# Reader1.net
KiCad netlist of a schematic drawn in EAGLE
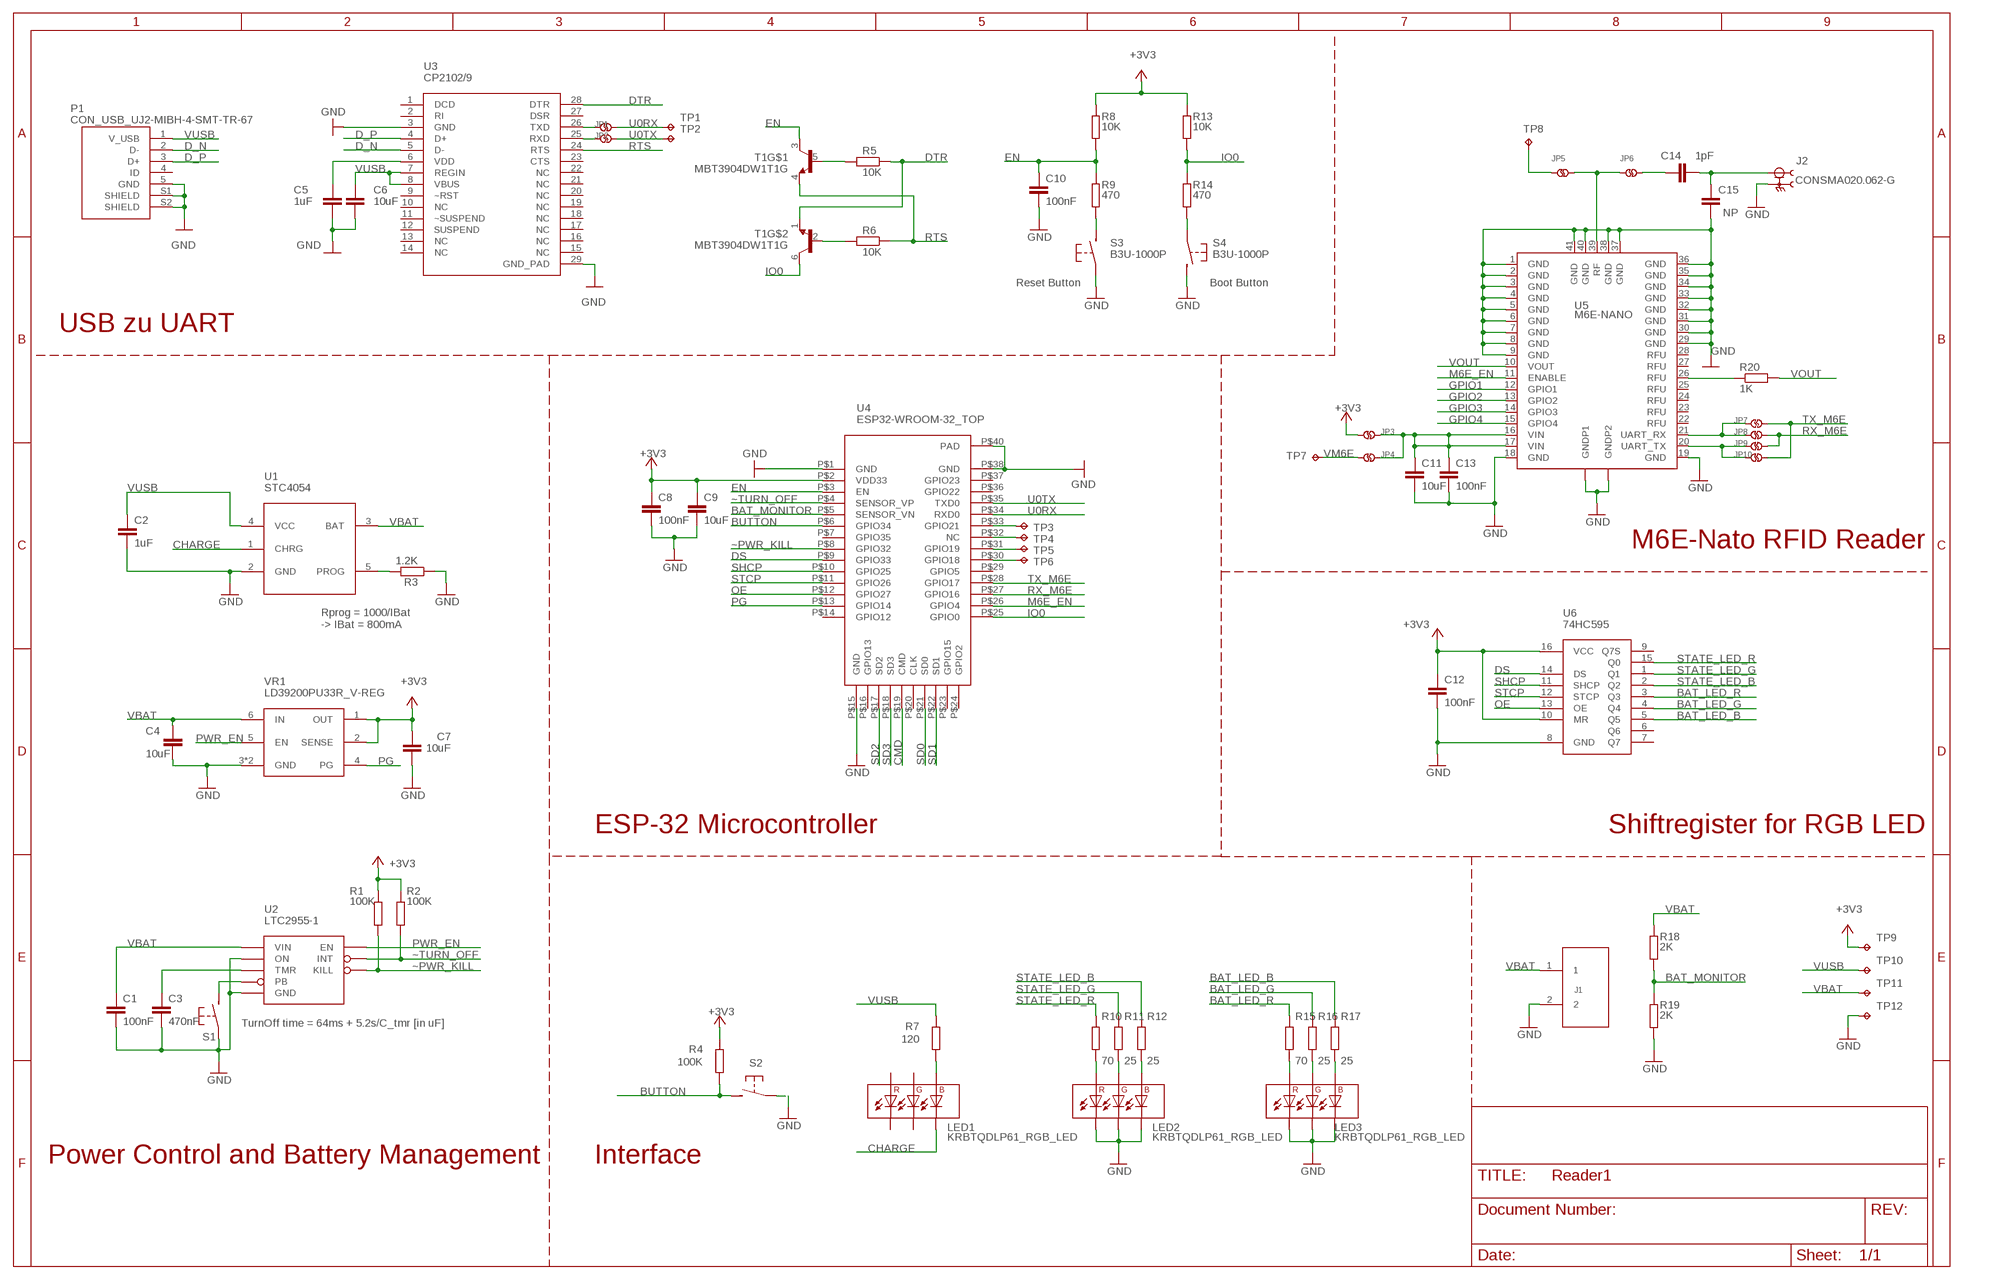
[diagram p0: schematic, sheet 1]

(export (version "E")
  (design (tool "Eeschema 10.0.6"))
  (components
    (comp (ref "C1")
      (value "100nF")
      (footprint "eagle-import:0603")
      (libsource (lib "eagle-import") (part "CAP_0603"))
    )
    (comp (ref "C2")
      (value "1uF")
      (footprint "eagle-import:0603")
      (libsource (lib "eagle-import") (part "CAP_0603"))
    )
    (comp (ref "C3")
      (value "470nF")
      (footprint "eagle-import:0603")
      (libsource (lib "eagle-import") (part "CAP_0603"))
    )
    (comp (ref "C4")
      (value "10uF")
      (footprint "eagle-import:0603")
      (libsource (lib "eagle-import") (part "CAP_0603"))
    )
    (comp (ref "C5")
      (value "1uF")
      (footprint "eagle-import:0603")
      (libsource (lib "eagle-import") (part "CAP_0603"))
    )
    (comp (ref "C6")
      (value "10uF")
      (footprint "eagle-import:0603")
      (libsource (lib "eagle-import") (part "CAP_0603"))
    )
    (comp (ref "C7")
      (value "10uF")
      (footprint "eagle-import:0603")
      (libsource (lib "eagle-import") (part "CAP_0603"))
    )
    (comp (ref "C8")
      (value "100nF")
      (footprint "eagle-import:0603")
      (libsource (lib "eagle-import") (part "CAP_0603"))
    )
    (comp (ref "C9")
      (value "10uF")
      (footprint "eagle-import:0603")
      (libsource (lib "eagle-import") (part "CAP_0603"))
    )
    (comp (ref "C10")
      (value "100nF")
      (footprint "eagle-import:0603")
      (libsource (lib "eagle-import") (part "CAP_0603"))
    )
    (comp (ref "C11")
      (value "10uF")
      (footprint "eagle-import:0603")
      (libsource (lib "eagle-import") (part "CAP_0603"))
    )
    (comp (ref "C12")
      (value "100nF")
      (footprint "eagle-import:0603")
      (libsource (lib "eagle-import") (part "CAP_0603"))
    )
    (comp (ref "C13")
      (value "100nF")
      (footprint "eagle-import:0603")
      (libsource (lib "eagle-import") (part "CAP_0603"))
    )
    (comp (ref "C14")
      (value "1pF")
      (footprint "eagle-import:0603")
      (libsource (lib "eagle-import") (part "CAP_0603"))
    )
    (comp (ref "C15")
      (value "NP")
      (footprint "eagle-import:0603")
      (libsource (lib "eagle-import") (part "CAP_0603"))
    )
    (comp (ref "J1")
      (value "CON_2")
      (footprint "eagle-import:CON_2")
      (libsource (lib "eagle-import") (part "CON_2"))
    )
    (comp (ref "J2")
      (value "CONSMA020.062-G")
      (footprint "eagle-import:LINX_CONSMA020.062-G")
      (fields
        (field (name "DIGI-KEY_PART_NUMBER") "343-CONSMA020.062-G-ND")
        (field (name "MF") "Linx Technologies")
      )
      (libsource (lib "eagle-import") (part "CONSMA020.062-G"))
    )
    (comp (ref "JP1")
      (value "SOLDER_JUMPER")
      (footprint "eagle-import:SOLDER_JUMPER")
      (libsource (lib "eagle-import") (part "SOLDER_JUMPER"))
    )
    (comp (ref "JP2")
      (value "SOLDER_JUMPER")
      (footprint "eagle-import:SOLDER_JUMPER")
      (libsource (lib "eagle-import") (part "SOLDER_JUMPER"))
    )
    (comp (ref "JP3")
      (value "SOLDER_JUMPER")
      (footprint "eagle-import:SOLDER_JUMPER")
      (libsource (lib "eagle-import") (part "SOLDER_JUMPER"))
    )
    (comp (ref "JP4")
      (value "SOLDER_JUMPER")
      (footprint "eagle-import:SOLDER_JUMPER")
      (libsource (lib "eagle-import") (part "SOLDER_JUMPER"))
    )
    (comp (ref "JP5")
      (value "SOLDER_JUMPER")
      (footprint "eagle-import:SOLDER_JUMPER")
      (libsource (lib "eagle-import") (part "SOLDER_JUMPER"))
    )
    (comp (ref "JP6")
      (value "SOLDER_JUMPER")
      (footprint "eagle-import:SOLDER_JUMPER")
      (libsource (lib "eagle-import") (part "SOLDER_JUMPER"))
    )
    (comp (ref "JP7")
      (value "SOLDER_JUMPER")
      (footprint "eagle-import:SOLDER_JUMPER")
      (libsource (lib "eagle-import") (part "SOLDER_JUMPER"))
    )
    (comp (ref "JP8")
      (value "SOLDER_JUMPER")
      (footprint "eagle-import:SOLDER_JUMPER")
      (libsource (lib "eagle-import") (part "SOLDER_JUMPER"))
    )
    (comp (ref "JP9")
      (value "SOLDER_JUMPER")
      (footprint "eagle-import:SOLDER_JUMPER")
      (libsource (lib "eagle-import") (part "SOLDER_JUMPER"))
    )
    (comp (ref "JP10")
      (value "SOLDER_JUMPER")
      (footprint "eagle-import:SOLDER_JUMPER")
      (libsource (lib "eagle-import") (part "SOLDER_JUMPER"))
    )
    (comp (ref "LED1")
      (value "KRBTQDLP61_RGB_LED")
      (footprint "eagle-import:KRBTQDLP61_RGB_LED")
      (libsource (lib "eagle-import") (part "KRBTQDLP61_RGB_LED"))
    )
    (comp (ref "LED2")
      (value "KRBTQDLP61_RGB_LED")
      (footprint "eagle-import:KRBTQDLP61_RGB_LED")
      (libsource (lib "eagle-import") (part "KRBTQDLP61_RGB_LED"))
    )
    (comp (ref "LED3")
      (value "KRBTQDLP61_RGB_LED")
      (footprint "eagle-import:KRBTQDLP61_RGB_LED")
      (libsource (lib "eagle-import") (part "KRBTQDLP61_RGB_LED"))
    )
    (comp (ref "P1")
      (value "CON_USB_UJ2-MIBH-4-SMT-TR-67")
      (footprint "eagle-import:CON_USB_UJ2-MIBH-4-SMT-TR-67")
      (libsource (lib "eagle-import") (part "CON_USB_UJ2-MIBH-4-SMT-TR-67"))
    )
    (comp (ref "R1")
      (value "100K")
      (footprint "eagle-import:0603")
      (libsource (lib "eagle-import") (part "RES_0603"))
    )
    (comp (ref "R2")
      (value "100K")
      (footprint "eagle-import:0603")
      (libsource (lib "eagle-import") (part "RES_0603"))
    )
    (comp (ref "R3")
      (value "1.2K")
      (footprint "eagle-import:0603")
      (libsource (lib "eagle-import") (part "RES_0603"))
    )
    (comp (ref "R4")
      (value "100K")
      (footprint "eagle-import:0603")
      (libsource (lib "eagle-import") (part "RES_0603"))
    )
    (comp (ref "R5")
      (value "10K")
      (footprint "eagle-import:0603")
      (libsource (lib "eagle-import") (part "RES_0603"))
    )
    (comp (ref "R6")
      (value "10K")
      (footprint "eagle-import:0603")
      (libsource (lib "eagle-import") (part "RES_0603"))
    )
    (comp (ref "R7")
      (value "120")
      (footprint "eagle-import:0603")
      (libsource (lib "eagle-import") (part "RES_0603"))
    )
    (comp (ref "R8")
      (value "10K")
      (footprint "eagle-import:0603")
      (libsource (lib "eagle-import") (part "RES_0603"))
    )
    (comp (ref "R9")
      (value "470")
      (footprint "eagle-import:0603")
      (libsource (lib "eagle-import") (part "RES_0603"))
    )
    (comp (ref "R10")
      (value "70")
      (footprint "eagle-import:0603")
      (libsource (lib "eagle-import") (part "RES_0603"))
    )
    (comp (ref "R11")
      (value "25")
      (footprint "eagle-import:0603")
      (libsource (lib "eagle-import") (part "RES_0603"))
    )
    (comp (ref "R12")
      (value "25")
      (footprint "eagle-import:0603")
      (libsource (lib "eagle-import") (part "RES_0603"))
    )
    (comp (ref "R13")
      (value "10K")
      (footprint "eagle-import:0603")
      (libsource (lib "eagle-import") (part "RES_0603"))
    )
    (comp (ref "R14")
      (value "470")
      (footprint "eagle-import:0603")
      (libsource (lib "eagle-import") (part "RES_0603"))
    )
    (comp (ref "R15")
      (value "70")
      (footprint "eagle-import:0603")
      (libsource (lib "eagle-import") (part "RES_0603"))
    )
    (comp (ref "R16")
      (value "25")
      (footprint "eagle-import:0603")
      (libsource (lib "eagle-import") (part "RES_0603"))
    )
    (comp (ref "R17")
      (value "25")
      (footprint "eagle-import:0603")
      (libsource (lib "eagle-import") (part "RES_0603"))
    )
    (comp (ref "R18")
      (value "2K")
      (footprint "eagle-import:0603")
      (libsource (lib "eagle-import") (part "RES_0603"))
    )
    (comp (ref "R19")
      (value "2K")
      (footprint "eagle-import:0603")
      (libsource (lib "eagle-import") (part "RES_0603"))
    )
    (comp (ref "R20")
      (value "1K")
      (footprint "eagle-import:0603")
      (libsource (lib "eagle-import") (part "RES_0603"))
    )
    (comp (ref "S1")
      (value "EG5358CT-ND_PB")
      (footprint "eagle-import:EG5358CT-ND_PB")
      (libsource (lib "eagle-import") (part "EG5358CT-ND_PB"))
    )
    (comp (ref "S2")
      (value "EG5358CT-ND_PB")
      (footprint "eagle-import:EG5358CT-ND_PB")
      (libsource (lib "eagle-import") (part "EG5358CT-ND_PB"))
    )
    (comp (ref "S3")
      (value "B3U-1000P")
      (footprint "eagle-import:B3U-1000P")
      (libsource (lib "eagle-import") (part "BUTTON_B3U-1000P"))
    )
    (comp (ref "S4")
      (value "B3U-1000P")
      (footprint "eagle-import:B3U-1000P")
      (libsource (lib "eagle-import") (part "BUTTON_B3U-1000P"))
    )
    (comp (ref "T1")
      (value "MBT3904DW1T1G")
      (footprint "eagle-import:SOT23-6")
      (libsource (lib "eagle-import") (part "MBT3904DW1T1G"))
    )
    (comp (ref "TP1")
      (value "TP")
      (footprint "eagle-import:TEST_PAD")
      (libsource (lib "eagle-import") (part "TP"))
    )
    (comp (ref "TP2")
      (value "TP")
      (footprint "eagle-import:TEST_PAD")
      (libsource (lib "eagle-import") (part "TP"))
    )
    (comp (ref "TP3")
      (value "TP")
      (footprint "eagle-import:TEST_PAD")
      (libsource (lib "eagle-import") (part "TP"))
    )
    (comp (ref "TP4")
      (value "TP")
      (footprint "eagle-import:TEST_PAD")
      (libsource (lib "eagle-import") (part "TP"))
    )
    (comp (ref "TP5")
      (value "TP")
      (footprint "eagle-import:TEST_PAD")
      (libsource (lib "eagle-import") (part "TP"))
    )
    (comp (ref "TP6")
      (value "TP")
      (footprint "eagle-import:TEST_PAD")
      (libsource (lib "eagle-import") (part "TP"))
    )
    (comp (ref "TP7")
      (value "TP")
      (footprint "eagle-import:TEST_PAD")
      (libsource (lib "eagle-import") (part "TP"))
    )
    (comp (ref "TP8")
      (value "TP")
      (footprint "eagle-import:TEST_PAD")
      (libsource (lib "eagle-import") (part "TP"))
    )
    (comp (ref "TP9")
      (value "TP")
      (footprint "eagle-import:TEST_PAD")
      (libsource (lib "eagle-import") (part "TP"))
    )
    (comp (ref "TP10")
      (value "TP")
      (footprint "eagle-import:TEST_PAD")
      (libsource (lib "eagle-import") (part "TP"))
    )
    (comp (ref "TP11")
      (value "TP")
      (footprint "eagle-import:TEST_PAD")
      (libsource (lib "eagle-import") (part "TP"))
    )
    (comp (ref "TP12")
      (value "TP")
      (footprint "eagle-import:TEST_PAD")
      (libsource (lib "eagle-import") (part "TP"))
    )
    (comp (ref "U1")
      (value "STC4054")
      (footprint "eagle-import:TSOT23-5L")
      (libsource (lib "eagle-import") (part "STC4054_BAT_CHARGER"))
    )
    (comp (ref "U2")
      (value "LTC2955-1")
      (footprint "eagle-import:SOT23-8")
      (libsource (lib "eagle-import") (part "LTC2955-1_ON/OFF_CTLR"))
    )
    (comp (ref "U3")
      (value "CP2102/9")
      (footprint "eagle-import:QFN-28")
      (libsource (lib "eagle-import") (part "CP2102/9"))
    )
    (comp (ref "U4")
      (value "ESP32-WROOM-32_TOP")
      (footprint "eagle-import:ESP32-WROOM-32_TOP")
      (libsource (lib "eagle-import") (part "ESP32-WROOM-32_TOP"))
    )
    (comp (ref "U5")
      (value "M6E-NANO")
      (footprint "eagle-import:M6E-NANO")
      (libsource (lib "eagle-import") (part "M6E-NANO"))
    )
    (comp (ref "U6")
      (value "74HC595")
      (footprint "eagle-import:SOIC-16")
      (libsource (lib "eagle-import") (part "74HC595_SHIFTREGISTER"))
    )
    (comp (ref "VR1")
      (value "LD39200PU33R_V-REG")
      (footprint "eagle-import:DFN-6")
      (libsource (lib "eagle-import") (part "LD39200PU33R_V-REG"))
    )
  )
  (nets
    (net (code "1") (name "+3V3") (class "Default")
      (node (ref "C12") (pin "1") (pinfunction "1_1") (pintype "passive"))
      (node (ref "C7") (pin "2") (pinfunction "2_2") (pintype "passive"))
      (node (ref "C8") (pin "1") (pinfunction "1_1") (pintype "passive"))
      (node (ref "C9") (pin "1") (pinfunction "1_1") (pintype "passive"))
      (node (ref "JP3") (pin "P$1") (pinfunction "P$1_P$1") (pintype "bidirectional"))
      (node (ref "R1") (pin "1") (pinfunction "1_1") (pintype "passive"))
      (node (ref "R13") (pin "2") (pinfunction "2_2") (pintype "passive"))
      (node (ref "R2") (pin "1") (pinfunction "1_1") (pintype "passive"))
      (node (ref "R4") (pin "2") (pinfunction "2_2") (pintype "passive"))
      (node (ref "R8") (pin "2") (pinfunction "2_2") (pintype "passive"))
      (node (ref "TP9") (pin "TP") (pinfunction "TP_TP") (pintype "input"))
      (node (ref "U4") (pin "P$2") (pinfunction "VDD33_P$2") (pintype "bidirectional"))
      (node (ref "U6") (pin "10") (pinfunction "MR_10") (pintype "bidirectional"))
      (node (ref "U6") (pin "16") (pinfunction "VCC_16") (pintype "bidirectional"))
      (node (ref "VR1") (pin "1") (pinfunction "OUT_1") (pintype "bidirectional"))
      (node (ref "VR1") (pin "2") (pinfunction "SENSE_2") (pintype "bidirectional"))
    )
    (net (code "2") (name "/BAT_LED_B") (class "Default")
      (node (ref "R17") (pin "2") (pinfunction "2_2") (pintype "passive"))
      (node (ref "U6") (pin "5") (pinfunction "Q5_5") (pintype "bidirectional"))
    )
    (net (code "3") (name "/BAT_LED_G") (class "Default")
      (node (ref "R16") (pin "2") (pinfunction "2_2") (pintype "passive"))
      (node (ref "U6") (pin "4") (pinfunction "Q4_4") (pintype "bidirectional"))
    )
    (net (code "4") (name "/BAT_LED_R") (class "Default")
      (node (ref "R15") (pin "2") (pinfunction "2_2") (pintype "passive"))
      (node (ref "U6") (pin "3") (pinfunction "Q3_3") (pintype "bidirectional"))
    )
    (net (code "5") (name "/BAT_MONITOR") (class "Default")
      (node (ref "R18") (pin "2") (pinfunction "2_2") (pintype "passive"))
      (node (ref "R19") (pin "1") (pinfunction "1_1") (pintype "passive"))
      (node (ref "U4") (pin "P$5") (pinfunction "SENSOR_VN_P$5") (pintype "bidirectional"))
    )
    (net (code "6") (name "/BUTTON") (class "Default")
      (node (ref "R4") (pin "1") (pinfunction "1_1") (pintype "passive"))
      (node (ref "S2") (pin "2") (pinfunction "S_2") (pintype "passive"))
      (node (ref "U4") (pin "P$6") (pinfunction "GPIO34_P$6") (pintype "bidirectional"))
    )
    (net (code "7") (name "/CHARGE") (class "Default")
      (node (ref "LED1") (pin "P$4") (pinfunction "BC_P$4") (pintype "passive"))
      (node (ref "U1") (pin "1") (pinfunction "CHRG_1") (pintype "bidirectional"))
    )
    (net (code "8") (name "/CMD") (class "Default")
      (node (ref "U4") (pin "P$19") (pinfunction "CMD_P$19") (pintype "bidirectional"))
    )
    (net (code "9") (name "/DS") (class "Default")
      (node (ref "U4") (pin "P$9") (pinfunction "GPIO33_P$9") (pintype "bidirectional"))
      (node (ref "U6") (pin "14") (pinfunction "DS_14") (pintype "bidirectional"))
    )
    (net (code "10") (name "/DTR") (class "Default")
      (node (ref "R5") (pin "1") (pinfunction "1_1") (pintype "passive"))
      (node (ref "T1") (pin "1") (pinfunction "E_1") (pintype "passive"))
      (node (ref "U3") (pin "28") (pinfunction "DTR_28") (pintype "bidirectional"))
    )
    (net (code "11") (name "/D_N") (class "Default")
      (node (ref "P1") (pin "2") (pinfunction "D-_2") (pintype "bidirectional"))
      (node (ref "U3") (pin "5") (pinfunction "D-_5") (pintype "bidirectional"))
    )
    (net (code "12") (name "/D_P") (class "Default")
      (node (ref "P1") (pin "3") (pinfunction "D+_3") (pintype "bidirectional"))
      (node (ref "U3") (pin "4") (pinfunction "D+_4") (pintype "bidirectional"))
    )
    (net (code "13") (name "/EN") (class "Default")
      (node (ref "C10") (pin "1") (pinfunction "1_1") (pintype "passive"))
      (node (ref "R8") (pin "1") (pinfunction "1_1") (pintype "passive"))
      (node (ref "R9") (pin "2") (pinfunction "2_2") (pintype "passive"))
      (node (ref "T1") (pin "3") (pinfunction "C_3") (pintype "passive"))
      (node (ref "U4") (pin "P$3") (pinfunction "EN_P$3") (pintype "bidirectional"))
    )
    (net (code "14") (name "/GPIO1") (class "Default")
      (node (ref "U5") (pin "12") (pinfunction "GPIO1_12") (pintype "bidirectional"))
    )
    (net (code "15") (name "/GPIO2") (class "Default")
      (node (ref "U5") (pin "13") (pinfunction "GPIO2_13") (pintype "bidirectional"))
    )
    (net (code "16") (name "/GPIO3") (class "Default")
      (node (ref "U5") (pin "14") (pinfunction "GPIO3_14") (pintype "bidirectional"))
    )
    (net (code "17") (name "/GPIO4") (class "Default")
      (node (ref "U5") (pin "15") (pinfunction "GPIO4_15") (pintype "bidirectional"))
    )
    (net (code "18") (name "/IO0") (class "Default")
      (node (ref "R13") (pin "1") (pinfunction "1_1") (pintype "passive"))
      (node (ref "R14") (pin "2") (pinfunction "2_2") (pintype "passive"))
      (node (ref "T1") (pin "6") (pinfunction "C_6") (pintype "passive"))
      (node (ref "U4") (pin "P$25") (pinfunction "GPIO0_P$25") (pintype "bidirectional"))
    )
    (net (code "19") (name "/M6E_EN") (class "Default")
      (node (ref "U4") (pin "P$26") (pinfunction "GPIO4_P$26") (pintype "bidirectional"))
      (node (ref "U5") (pin "11") (pinfunction "ENABLE_11") (pintype "bidirectional"))
    )
    (net (code "20") (name "/OE") (class "Default")
      (node (ref "U4") (pin "P$12") (pinfunction "GPIO27_P$12") (pintype "bidirectional"))
      (node (ref "U6") (pin "13") (pinfunction "OE_13") (pintype "bidirectional"))
    )
    (net (code "21") (name "/PG") (class "Default")
      (node (ref "U4") (pin "P$13") (pinfunction "GPIO14_P$13") (pintype "bidirectional"))
      (node (ref "VR1") (pin "4") (pinfunction "PG_4") (pintype "bidirectional"))
    )
    (net (code "22") (name "/PWR_EN") (class "Default")
      (node (ref "U2") (pin "7") (pinfunction "EN_7") (pintype "bidirectional"))
      (node (ref "VR1") (pin "5") (pinfunction "EN_5") (pintype "bidirectional"))
    )
    (net (code "23") (name "/RTS") (class "Default")
      (node (ref "R6") (pin "1") (pinfunction "1_1") (pintype "passive"))
      (node (ref "T1") (pin "4") (pinfunction "E_4") (pintype "passive"))
      (node (ref "U3") (pin "24") (pinfunction "RTS_24") (pintype "bidirectional"))
    )
    (net (code "24") (name "/RX_M6E") (class "Default")
      (node (ref "JP8") (pin "P$2") (pinfunction "P$2_P$2") (pintype "bidirectional"))
      (node (ref "JP9") (pin "P$2") (pinfunction "P$2_P$2") (pintype "bidirectional"))
      (node (ref "U4") (pin "P$27") (pinfunction "GPIO16_P$27") (pintype "bidirectional"))
    )
    (net (code "25") (name "/SD0") (class "Default")
      (node (ref "U4") (pin "P$21") (pinfunction "SD0_P$21") (pintype "bidirectional"))
    )
    (net (code "26") (name "/SD1") (class "Default")
      (node (ref "U4") (pin "P$22") (pinfunction "SD1_P$22") (pintype "bidirectional"))
    )
    (net (code "27") (name "/SD2") (class "Default")
      (node (ref "U4") (pin "P$17") (pinfunction "SD2_P$17") (pintype "bidirectional"))
    )
    (net (code "28") (name "/SD3") (class "Default")
      (node (ref "U4") (pin "P$18") (pinfunction "SD3_P$18") (pintype "bidirectional"))
    )
    (net (code "29") (name "/SHCP") (class "Default")
      (node (ref "U4") (pin "P$10") (pinfunction "GPIO25_P$10") (pintype "bidirectional"))
      (node (ref "U6") (pin "11") (pinfunction "SHCP_11") (pintype "bidirectional"))
    )
    (net (code "30") (name "/STATE_LED_B") (class "Default")
      (node (ref "R12") (pin "2") (pinfunction "2_2") (pintype "passive"))
      (node (ref "U6") (pin "2") (pinfunction "Q2_2") (pintype "bidirectional"))
    )
    (net (code "31") (name "/STATE_LED_G") (class "Default")
      (node (ref "R11") (pin "2") (pinfunction "2_2") (pintype "passive"))
      (node (ref "U6") (pin "1") (pinfunction "Q1_1") (pintype "bidirectional"))
    )
    (net (code "32") (name "/STATE_LED_R") (class "Default")
      (node (ref "R10") (pin "2") (pinfunction "2_2") (pintype "passive"))
      (node (ref "U6") (pin "15") (pinfunction "Q0_15") (pintype "bidirectional"))
    )
    (net (code "33") (name "/STCP") (class "Default")
      (node (ref "U4") (pin "P$11") (pinfunction "GPIO26_P$11") (pintype "bidirectional"))
      (node (ref "U6") (pin "12") (pinfunction "STCP_12") (pintype "bidirectional"))
    )
    (net (code "34") (name "/TX_M6E") (class "Default")
      (node (ref "JP10") (pin "P$2") (pinfunction "P$2_P$2") (pintype "bidirectional"))
      (node (ref "JP7") (pin "P$2") (pinfunction "P$2_P$2") (pintype "bidirectional"))
      (node (ref "U4") (pin "P$28") (pinfunction "GPIO17_P$28") (pintype "bidirectional"))
    )
    (net (code "35") (name "/U0RX") (class "Default")
      (node (ref "JP1") (pin "P$2") (pinfunction "P$2_P$2") (pintype "bidirectional"))
      (node (ref "TP1") (pin "TP") (pinfunction "TP_TP") (pintype "input"))
      (node (ref "U4") (pin "P$34") (pinfunction "RXD0_P$34") (pintype "bidirectional"))
    )
    (net (code "36") (name "/U0TX") (class "Default")
      (node (ref "JP2") (pin "P$2") (pinfunction "P$2_P$2") (pintype "bidirectional"))
      (node (ref "TP2") (pin "TP") (pinfunction "TP_TP") (pintype "input"))
      (node (ref "U4") (pin "P$35") (pinfunction "TXD0_P$35") (pintype "bidirectional"))
    )
    (net (code "37") (name "/VBAT") (class "Default")
      (node (ref "C1") (pin "1") (pinfunction "1_1") (pintype "passive"))
      (node (ref "C4") (pin "1") (pinfunction "1_1") (pintype "passive"))
      (node (ref "J1") (pin "1") (pinfunction "1_1") (pintype "bidirectional"))
      (node (ref "R18") (pin "1") (pinfunction "1_1") (pintype "passive"))
      (node (ref "TP11") (pin "TP") (pinfunction "TP_TP") (pintype "input"))
      (node (ref "U1") (pin "3") (pinfunction "BAT_3") (pintype "bidirectional"))
      (node (ref "U2") (pin "6") (pinfunction "VIN_6") (pintype "bidirectional"))
      (node (ref "VR1") (pin "6") (pinfunction "IN_6") (pintype "bidirectional"))
    )
    (net (code "38") (name "/VM6E") (class "Default")
      (node (ref "JP4") (pin "P$1") (pinfunction "P$1_P$1") (pintype "bidirectional"))
      (node (ref "TP7") (pin "TP") (pinfunction "TP_TP") (pintype "input"))
    )
    (net (code "39") (name "/VOUT") (class "Default")
      (node (ref "R20") (pin "2") (pinfunction "2_2") (pintype "passive"))
      (node (ref "U5") (pin "10") (pinfunction "VOUT_10") (pintype "bidirectional"))
    )
    (net (code "40") (name "/VUSB") (class "Default")
      (node (ref "C2") (pin "1") (pinfunction "1_1") (pintype "passive"))
      (node (ref "C6") (pin "1") (pinfunction "1_1") (pintype "passive"))
      (node (ref "P1") (pin "1") (pinfunction "V_USB_1") (pintype "bidirectional"))
      (node (ref "R7") (pin "2") (pinfunction "2_2") (pintype "passive"))
      (node (ref "TP10") (pin "TP") (pinfunction "TP_TP") (pintype "input"))
      (node (ref "U1") (pin "4") (pinfunction "VCC_4") (pintype "bidirectional"))
      (node (ref "U3") (pin "7") (pinfunction "REGIN_7") (pintype "bidirectional"))
      (node (ref "U3") (pin "8") (pinfunction "VBUS_8") (pintype "bidirectional"))
    )
    (net (code "41") (name "/~{PWR_KILL}") (class "Default")
      (node (ref "R1") (pin "2") (pinfunction "2_2") (pintype "passive"))
      (node (ref "U2") (pin "2") (pinfunction "KILL_2") (pintype "bidirectional"))
      (node (ref "U4") (pin "P$8") (pinfunction "GPIO32_P$8") (pintype "bidirectional"))
    )
    (net (code "42") (name "/~{TURN_OFF}") (class "Default")
      (node (ref "R2") (pin "2") (pinfunction "2_2") (pintype "passive"))
      (node (ref "U2") (pin "8") (pinfunction "INT_8") (pintype "bidirectional"))
      (node (ref "U4") (pin "P$4") (pinfunction "SENSOR_VP_P$4") (pintype "bidirectional"))
    )
    (net (code "43") (name "GND") (class "Default")
      (node (ref "C1") (pin "2") (pinfunction "2_2") (pintype "passive"))
      (node (ref "C10") (pin "2") (pinfunction "2_2") (pintype "passive"))
      (node (ref "C11") (pin "2") (pinfunction "2_2") (pintype "passive"))
      (node (ref "C12") (pin "2") (pinfunction "2_2") (pintype "passive"))
      (node (ref "C13") (pin "2") (pinfunction "2_2") (pintype "passive"))
      (node (ref "C15") (pin "1") (pinfunction "1_1") (pintype "passive"))
      (node (ref "C2") (pin "2") (pinfunction "2_2") (pintype "passive"))
      (node (ref "C3") (pin "2") (pinfunction "2_2") (pintype "passive"))
      (node (ref "C4") (pin "2") (pinfunction "2_2") (pintype "passive"))
      (node (ref "C5") (pin "2") (pinfunction "2_2") (pintype "passive"))
      (node (ref "C6") (pin "2") (pinfunction "2_2") (pintype "passive"))
      (node (ref "C7") (pin "1") (pinfunction "1_1") (pintype "passive"))
      (node (ref "C8") (pin "2") (pinfunction "2_2") (pintype "passive"))
      (node (ref "C9") (pin "2") (pinfunction "2_2") (pintype "passive"))
      (node (ref "J1") (pin "2") (pinfunction "2_2") (pintype "bidirectional"))
      (node (ref "J2") (pin "S1") (pinfunction "2_S1") (pintype "passive"))
      (node (ref "J2") (pin "S2") (pinfunction "2_S2") (pintype "passive"))
      (node (ref "J2") (pin "S3") (pinfunction "2_S3") (pintype "passive"))
      (node (ref "J2") (pin "S4") (pinfunction "2_S4") (pintype "passive"))
      (node (ref "LED2") (pin "P$3") (pinfunction "GC_P$3") (pintype "passive"))
      (node (ref "LED2") (pin "P$4") (pinfunction "BC_P$4") (pintype "passive"))
      (node (ref "LED2") (pin "P$6") (pinfunction "RC_P$6") (pintype "passive"))
      (node (ref "LED3") (pin "P$3") (pinfunction "GC_P$3") (pintype "passive"))
      (node (ref "LED3") (pin "P$4") (pinfunction "BC_P$4") (pintype "passive"))
      (node (ref "LED3") (pin "P$6") (pinfunction "RC_P$6") (pintype "passive"))
      (node (ref "P1") (pin "5") (pinfunction "GND_5") (pintype "bidirectional"))
      (node (ref "P1") (pin "S1") (pinfunction "SHIELD_S1") (pintype "bidirectional"))
      (node (ref "P1") (pin "S2") (pinfunction "SHIELD_S2") (pintype "bidirectional"))
      (node (ref "R19") (pin "2") (pinfunction "2_2") (pintype "passive"))
      (node (ref "R3") (pin "1") (pinfunction "1_1") (pintype "passive"))
      (node (ref "S1") (pin "1") (pinfunction "P_1") (pintype "passive"))
      (node (ref "S1") (pin "S1") (pinfunction "P_S1") (pintype "passive"))
      (node (ref "S1") (pin "S2") (pinfunction "P_S2") (pintype "passive"))
      (node (ref "S2") (pin "1") (pinfunction "P_1") (pintype "passive"))
      (node (ref "S2") (pin "S1") (pinfunction "P_S1") (pintype "passive"))
      (node (ref "S2") (pin "S2") (pinfunction "P_S2") (pintype "passive"))
      (node (ref "S3") (pin "P$1") (pinfunction "P_P$1") (pintype "passive"))
      (node (ref "S4") (pin "P$2") (pinfunction "S_P$2") (pintype "passive"))
      (node (ref "TP12") (pin "TP") (pinfunction "TP_TP") (pintype "input"))
      (node (ref "U1") (pin "2") (pinfunction "GND_2") (pintype "bidirectional"))
      (node (ref "U2") (pin "1") (pinfunction "ON_1") (pintype "bidirectional"))
      (node (ref "U2") (pin "4") (pinfunction "GND_4") (pintype "bidirectional"))
      (node (ref "U3") (pin "29") (pinfunction "GND_PAD_29") (pintype "bidirectional"))
      (node (ref "U3") (pin "3") (pinfunction "GND_3") (pintype "bidirectional"))
      (node (ref "U4") (pin "P$1") (pinfunction "GND_P$1") (pintype "bidirectional"))
      (node (ref "U4") (pin "P$15") (pinfunction "GND_P$15") (pintype "bidirectional"))
      (node (ref "U4") (pin "P$38") (pinfunction "GND_P$38") (pintype "bidirectional"))
      (node (ref "U4") (pin "P$40") (pinfunction "PAD_P$40") (pintype "bidirectional"))
      (node (ref "U5") (pin "1") (pinfunction "GND_1") (pintype "bidirectional"))
      (node (ref "U5") (pin "18") (pinfunction "GND_18") (pintype "bidirectional"))
      (node (ref "U5") (pin "19") (pinfunction "GND_19") (pintype "bidirectional"))
      (node (ref "U5") (pin "2") (pinfunction "GND_2") (pintype "bidirectional"))
      (node (ref "U5") (pin "29") (pinfunction "GND_29") (pintype "bidirectional"))
      (node (ref "U5") (pin "3") (pinfunction "GND_3") (pintype "bidirectional"))
      (node (ref "U5") (pin "30") (pinfunction "GND_30") (pintype "bidirectional"))
      (node (ref "U5") (pin "31") (pinfunction "GND_31") (pintype "bidirectional"))
      (node (ref "U5") (pin "32") (pinfunction "GND_32") (pintype "bidirectional"))
      (node (ref "U5") (pin "33") (pinfunction "GND_33") (pintype "bidirectional"))
      (node (ref "U5") (pin "34") (pinfunction "GND_34") (pintype "bidirectional"))
      (node (ref "U5") (pin "35") (pinfunction "GND_35") (pintype "bidirectional"))
      (node (ref "U5") (pin "36") (pinfunction "GND_36") (pintype "bidirectional"))
      (node (ref "U5") (pin "37") (pinfunction "GND_37") (pintype "bidirectional"))
      (node (ref "U5") (pin "38") (pinfunction "GND_38") (pintype "bidirectional"))
      (node (ref "U5") (pin "4") (pinfunction "GND_4") (pintype "bidirectional"))
      (node (ref "U5") (pin "40") (pinfunction "GND_40") (pintype "bidirectional"))
      (node (ref "U5") (pin "41") (pinfunction "GND_41") (pintype "bidirectional"))
      (node (ref "U5") (pin "5") (pinfunction "GND_5") (pintype "bidirectional"))
      (node (ref "U5") (pin "6") (pinfunction "GND_6") (pintype "bidirectional"))
      (node (ref "U5") (pin "7") (pinfunction "GND_7") (pintype "bidirectional"))
      (node (ref "U5") (pin "8") (pinfunction "GND_8") (pintype "bidirectional"))
      (node (ref "U5") (pin "9") (pinfunction "GND_9") (pintype "bidirectional"))
      (node (ref "U5") (pin "GND_PAD1") (pinfunction "GNDP1_GND_PAD1") (pintype "bidirectional"))
      (node (ref "U5") (pin "GND_PAD2") (pinfunction "GNDP2_GND_PAD2") (pintype "bidirectional"))
      (node (ref "U6") (pin "8") (pinfunction "GND_8") (pintype "bidirectional"))
      (node (ref "VR1") (pin "3") (pinfunction "GND_3") (pintype "bidirectional"))
      (node (ref "VR1") (pin "7") (pinfunction "GND_7") (pintype "bidirectional"))
    )
    (net (code "44") (name "Net-(C11-Pad1)") (class "Default")
      (node (ref "C11") (pin "1") (pinfunction "1_1") (pintype "passive"))
      (node (ref "C13") (pin "1") (pinfunction "1_1") (pintype "passive"))
      (node (ref "JP3") (pin "P$2") (pinfunction "P$2_P$2") (pintype "bidirectional"))
      (node (ref "JP4") (pin "P$2") (pinfunction "P$2_P$2") (pintype "bidirectional"))
      (node (ref "U5") (pin "16") (pinfunction "VIN_16") (pintype "bidirectional"))
      (node (ref "U5") (pin "17") (pinfunction "VIN_17") (pintype "bidirectional"))
    )
    (net (code "45") (name "Net-(C14-Pad1)") (class "Default")
      (node (ref "C14") (pin "1") (pinfunction "1_1") (pintype "passive"))
      (node (ref "JP6") (pin "P$2") (pinfunction "P$2_P$2") (pintype "bidirectional"))
    )
    (net (code "46") (name "Net-(C14-Pad2)") (class "Default")
      (node (ref "C14") (pin "2") (pinfunction "2_2") (pintype "passive"))
      (node (ref "C15") (pin "2") (pinfunction "2_2") (pintype "passive"))
      (node (ref "J2") (pin "1") (pinfunction "1_1") (pintype "passive"))
    )
    (net (code "47") (name "Net-(JP5-PadP$1)") (class "Default")
      (node (ref "JP5") (pin "P$1") (pinfunction "P$1_P$1") (pintype "bidirectional"))
      (node (ref "TP8") (pin "TP") (pinfunction "TP_TP") (pintype "input"))
    )
    (net (code "48") (name "Net-(LED1-BA)") (class "Default")
      (node (ref "LED1") (pin "P$2") (pinfunction "BA_P$2") (pintype "passive"))
      (node (ref "R7") (pin "1") (pinfunction "1_1") (pintype "passive"))
    )
    (net (code "49") (name "Net-(LED2-BA)") (class "Default")
      (node (ref "LED2") (pin "P$2") (pinfunction "BA_P$2") (pintype "passive"))
      (node (ref "R12") (pin "1") (pinfunction "1_1") (pintype "passive"))
    )
    (net (code "50") (name "Net-(LED2-GA)") (class "Default")
      (node (ref "LED2") (pin "P$1") (pinfunction "GA_P$1") (pintype "passive"))
      (node (ref "R11") (pin "1") (pinfunction "1_1") (pintype "passive"))
    )
    (net (code "51") (name "Net-(LED2-RA)") (class "Default")
      (node (ref "LED2") (pin "P$5") (pinfunction "RA_P$5") (pintype "passive"))
      (node (ref "R10") (pin "1") (pinfunction "1_1") (pintype "passive"))
    )
    (net (code "52") (name "Net-(LED3-BA)") (class "Default")
      (node (ref "LED3") (pin "P$2") (pinfunction "BA_P$2") (pintype "passive"))
      (node (ref "R17") (pin "1") (pinfunction "1_1") (pintype "passive"))
    )
    (net (code "53") (name "Net-(LED3-GA)") (class "Default")
      (node (ref "LED3") (pin "P$1") (pinfunction "GA_P$1") (pintype "passive"))
      (node (ref "R16") (pin "1") (pinfunction "1_1") (pintype "passive"))
    )
    (net (code "54") (name "Net-(LED3-RA)") (class "Default")
      (node (ref "LED3") (pin "P$5") (pinfunction "RA_P$5") (pintype "passive"))
      (node (ref "R15") (pin "1") (pinfunction "1_1") (pintype "passive"))
    )
    (net (code "55") (name "Net-(R20-Pad1)") (class "Default")
      (node (ref "R20") (pin "1") (pinfunction "1_1") (pintype "passive"))
      (node (ref "U5") (pin "26") (pinfunction "RFU_26") (pintype "bidirectional"))
    )
    (net (code "56") (name "Net-(S1-S)") (class "Default")
      (node (ref "S1") (pin "2") (pinfunction "S_2") (pintype "passive"))
      (node (ref "U2") (pin "5") (pinfunction "PB_5") (pintype "bidirectional"))
    )
    (net (code "57") (name "Net-(S3-S)") (class "Default")
      (node (ref "R9") (pin "1") (pinfunction "1_1") (pintype "passive"))
      (node (ref "S3") (pin "P$2") (pinfunction "S_P$2") (pintype "passive"))
    )
    (net (code "58") (name "Net-(S4-P)") (class "Default")
      (node (ref "R14") (pin "1") (pinfunction "1_1") (pintype "passive"))
      (node (ref "S4") (pin "P$1") (pinfunction "P_P$1") (pintype "passive"))
    )
    (net (code "59") (name "Net-(T1A-B)") (class "Default")
      (node (ref "R5") (pin "2") (pinfunction "2_2") (pintype "passive"))
      (node (ref "T1") (pin "5") (pinfunction "B_5") (pintype "passive"))
    )
    (net (code "60") (name "Net-(T1B-B)") (class "Default")
      (node (ref "R6") (pin "2") (pinfunction "2_2") (pintype "passive"))
      (node (ref "T1") (pin "2") (pinfunction "B_2") (pintype "passive"))
    )
    (net (code "61") (name "Net-(U1-PROG)") (class "Default")
      (node (ref "R3") (pin "2") (pinfunction "2_2") (pintype "passive"))
      (node (ref "U1") (pin "5") (pinfunction "PROG_5") (pintype "bidirectional"))
    )
    (net (code "62") (name "Net-(U2-TMR)") (class "Default")
      (node (ref "C3") (pin "1") (pinfunction "1_1") (pintype "passive"))
      (node (ref "U2") (pin "3") (pinfunction "TMR_3") (pintype "bidirectional"))
    )
    (net (code "63") (name "Net-(U3-RXD)") (class "Default")
      (node (ref "JP2") (pin "P$1") (pinfunction "P$1_P$1") (pintype "bidirectional"))
      (node (ref "U3") (pin "25") (pinfunction "RXD_25") (pintype "bidirectional"))
    )
    (net (code "64") (name "Net-(U3-TXD)") (class "Default")
      (node (ref "JP1") (pin "P$1") (pinfunction "P$1_P$1") (pintype "bidirectional"))
      (node (ref "U3") (pin "26") (pinfunction "TXD_26") (pintype "bidirectional"))
    )
    (net (code "65") (name "Net-(U3-VDD)") (class "Default")
      (node (ref "C5") (pin "1") (pinfunction "1_1") (pintype "passive"))
      (node (ref "U3") (pin "6") (pinfunction "VDD_6") (pintype "bidirectional"))
    )
    (net (code "66") (name "Net-(U4-GPIO18)") (class "Default")
      (node (ref "TP6") (pin "TP") (pinfunction "TP_TP") (pintype "input"))
      (node (ref "U4") (pin "P$30") (pinfunction "GPIO18_P$30") (pintype "bidirectional"))
    )
    (net (code "67") (name "Net-(U4-GPIO19)") (class "Default")
      (node (ref "TP5") (pin "TP") (pinfunction "TP_TP") (pintype "input"))
      (node (ref "U4") (pin "P$31") (pinfunction "GPIO19_P$31") (pintype "bidirectional"))
    )
    (net (code "68") (name "Net-(U4-GPIO21)") (class "Default")
      (node (ref "TP3") (pin "TP") (pinfunction "TP_TP") (pintype "input"))
      (node (ref "U4") (pin "P$33") (pinfunction "GPIO21_P$33") (pintype "bidirectional"))
    )
    (net (code "69") (name "Net-(U4-NC)") (class "Default")
      (node (ref "TP4") (pin "TP") (pinfunction "TP_TP") (pintype "input"))
      (node (ref "U4") (pin "P$32") (pinfunction "NC_P$32") (pintype "bidirectional"))
    )
    (net (code "70") (name "Net-(U5-RF)") (class "Default")
      (node (ref "JP5") (pin "P$2") (pinfunction "P$2_P$2") (pintype "bidirectional"))
      (node (ref "JP6") (pin "P$1") (pinfunction "P$1_P$1") (pintype "bidirectional"))
      (node (ref "U5") (pin "39") (pinfunction "RF_39") (pintype "bidirectional"))
    )
    (net (code "71") (name "Net-(U5-UART_RX)") (class "Default")
      (node (ref "JP7") (pin "P$1") (pinfunction "P$1_P$1") (pintype "bidirectional"))
      (node (ref "JP8") (pin "P$1") (pinfunction "P$1_P$1") (pintype "bidirectional"))
      (node (ref "U5") (pin "21") (pinfunction "UART_RX_21") (pintype "bidirectional"))
    )
    (net (code "72") (name "Net-(U5-UART_TX)") (class "Default")
      (node (ref "JP10") (pin "P$1") (pinfunction "P$1_P$1") (pintype "bidirectional"))
      (node (ref "JP9") (pin "P$1") (pinfunction "P$1_P$1") (pintype "bidirectional"))
      (node (ref "U5") (pin "20") (pinfunction "UART_TX_20") (pintype "bidirectional"))
    )
    (net (code "73") (name "unconnected-(LED1-GA-PadP$1)") (class "Default")
      (node (ref "LED1") (pin "P$1") (pinfunction "GA_P$1") (pintype "passive"))
    )
    (net (code "74") (name "unconnected-(LED1-GC-PadP$3)") (class "Default")
      (node (ref "LED1") (pin "P$3") (pinfunction "GC_P$3") (pintype "passive"))
    )
    (net (code "75") (name "unconnected-(LED1-RA-PadP$5)") (class "Default")
      (node (ref "LED1") (pin "P$5") (pinfunction "RA_P$5") (pintype "passive"))
    )
    (net (code "76") (name "unconnected-(LED1-RC-PadP$6)") (class "Default")
      (node (ref "LED1") (pin "P$6") (pinfunction "RC_P$6") (pintype "passive"))
    )
    (net (code "77") (name "unconnected-(P1-ID-Pad4)") (class "Default")
      (node (ref "P1") (pin "4") (pinfunction "ID_4") (pintype "bidirectional"))
    )
    (net (code "78") (name "unconnected-(U3-CTS-Pad23)") (class "Default")
      (node (ref "U3") (pin "23") (pinfunction "CTS_23") (pintype "bidirectional"))
    )
    (net (code "79") (name "unconnected-(U3-DCD-Pad1)") (class "Default")
      (node (ref "U3") (pin "1") (pinfunction "DCD_1") (pintype "bidirectional"))
    )
    (net (code "80") (name "unconnected-(U3-DSR-Pad27)") (class "Default")
      (node (ref "U3") (pin "27") (pinfunction "DSR_27") (pintype "bidirectional"))
    )
    (net (code "81") (name "unconnected-(U3-NC-Pad10)") (class "Default")
      (node (ref "U3") (pin "10") (pinfunction "NC_10") (pintype "bidirectional"))
    )
    (net (code "82") (name "unconnected-(U3-NC-Pad13)") (class "Default")
      (node (ref "U3") (pin "13") (pinfunction "NC_13") (pintype "bidirectional"))
    )
    (net (code "83") (name "unconnected-(U3-NC-Pad14)") (class "Default")
      (node (ref "U3") (pin "14") (pinfunction "NC_14") (pintype "bidirectional"))
    )
    (net (code "84") (name "unconnected-(U3-NC-Pad15)") (class "Default")
      (node (ref "U3") (pin "15") (pinfunction "NC_15") (pintype "bidirectional"))
    )
    (net (code "85") (name "unconnected-(U3-NC-Pad16)") (class "Default")
      (node (ref "U3") (pin "16") (pinfunction "NC_16") (pintype "bidirectional"))
    )
    (net (code "86") (name "unconnected-(U3-NC-Pad17)") (class "Default")
      (node (ref "U3") (pin "17") (pinfunction "NC_17") (pintype "bidirectional"))
    )
    (net (code "87") (name "unconnected-(U3-NC-Pad18)") (class "Default")
      (node (ref "U3") (pin "18") (pinfunction "NC_18") (pintype "bidirectional"))
    )
    (net (code "88") (name "unconnected-(U3-NC-Pad19)") (class "Default")
      (node (ref "U3") (pin "19") (pinfunction "NC_19") (pintype "bidirectional"))
    )
    (net (code "89") (name "unconnected-(U3-NC-Pad20)") (class "Default")
      (node (ref "U3") (pin "20") (pinfunction "NC_20") (pintype "bidirectional"))
    )
    (net (code "90") (name "unconnected-(U3-NC-Pad21)") (class "Default")
      (node (ref "U3") (pin "21") (pinfunction "NC_21") (pintype "bidirectional"))
    )
    (net (code "91") (name "unconnected-(U3-NC-Pad22)") (class "Default")
      (node (ref "U3") (pin "22") (pinfunction "NC_22") (pintype "bidirectional"))
    )
    (net (code "92") (name "unconnected-(U3-RI-Pad2)") (class "Default")
      (node (ref "U3") (pin "2") (pinfunction "RI_2") (pintype "bidirectional"))
    )
    (net (code "93") (name "unconnected-(U3-SUSPEND-Pad12)") (class "Default")
      (node (ref "U3") (pin "12") (pinfunction "SUSPEND_12") (pintype "bidirectional"))
    )
    (net (code "94") (name "unconnected-(U3-~{RST}-Pad9)") (class "Default")
      (node (ref "U3") (pin "9") (pinfunction "~{RST}_9") (pintype "bidirectional"))
    )
    (net (code "95") (name "unconnected-(U3-~{SUSPEND}-Pad11)") (class "Default")
      (node (ref "U3") (pin "11") (pinfunction "~{SUSPEND}_11") (pintype "bidirectional"))
    )
    (net (code "96") (name "unconnected-(U4-CLK-PadP$20)") (class "Default")
      (node (ref "U4") (pin "P$20") (pinfunction "CLK_P$20") (pintype "bidirectional"))
    )
    (net (code "97") (name "unconnected-(U4-GPIO2-PadP$24)") (class "Default")
      (node (ref "U4") (pin "P$24") (pinfunction "GPIO2_P$24") (pintype "bidirectional"))
    )
    (net (code "98") (name "unconnected-(U4-GPIO5-PadP$29)") (class "Default")
      (node (ref "U4") (pin "P$29") (pinfunction "GPIO5_P$29") (pintype "bidirectional"))
    )
    (net (code "99") (name "unconnected-(U4-GPIO12-PadP$14)") (class "Default")
      (node (ref "U4") (pin "P$14") (pinfunction "GPIO12_P$14") (pintype "bidirectional"))
    )
    (net (code "100") (name "unconnected-(U4-GPIO13-PadP$16)") (class "Default")
      (node (ref "U4") (pin "P$16") (pinfunction "GPIO13_P$16") (pintype "bidirectional"))
    )
    (net (code "101") (name "unconnected-(U4-GPIO15-PadP$23)") (class "Default")
      (node (ref "U4") (pin "P$23") (pinfunction "GPIO15_P$23") (pintype "bidirectional"))
    )
    (net (code "102") (name "unconnected-(U4-GPIO22-PadP$36)") (class "Default")
      (node (ref "U4") (pin "P$36") (pinfunction "GPIO22_P$36") (pintype "bidirectional"))
    )
    (net (code "103") (name "unconnected-(U4-GPIO23-PadP$37)") (class "Default")
      (node (ref "U4") (pin "P$37") (pinfunction "GPIO23_P$37") (pintype "bidirectional"))
    )
    (net (code "104") (name "unconnected-(U4-GPIO35-PadP$7)") (class "Default")
      (node (ref "U4") (pin "P$7") (pinfunction "GPIO35_P$7") (pintype "bidirectional"))
    )
    (net (code "105") (name "unconnected-(U5-RFU-Pad22)") (class "Default")
      (node (ref "U5") (pin "22") (pinfunction "RFU_22") (pintype "bidirectional"))
    )
    (net (code "106") (name "unconnected-(U5-RFU-Pad23)") (class "Default")
      (node (ref "U5") (pin "23") (pinfunction "RFU_23") (pintype "bidirectional"))
    )
    (net (code "107") (name "unconnected-(U5-RFU-Pad24)") (class "Default")
      (node (ref "U5") (pin "24") (pinfunction "RFU_24") (pintype "bidirectional"))
    )
    (net (code "108") (name "unconnected-(U5-RFU-Pad25)") (class "Default")
      (node (ref "U5") (pin "25") (pinfunction "RFU_25") (pintype "bidirectional"))
    )
    (net (code "109") (name "unconnected-(U5-RFU-Pad27)") (class "Default")
      (node (ref "U5") (pin "27") (pinfunction "RFU_27") (pintype "bidirectional"))
    )
    (net (code "110") (name "unconnected-(U5-RFU-Pad28)") (class "Default")
      (node (ref "U5") (pin "28") (pinfunction "RFU_28") (pintype "bidirectional"))
    )
    (net (code "111") (name "unconnected-(U6-Q6-Pad6)") (class "Default")
      (node (ref "U6") (pin "6") (pinfunction "Q6_6") (pintype "bidirectional"))
    )
    (net (code "112") (name "unconnected-(U6-Q7-Pad7)") (class "Default")
      (node (ref "U6") (pin "7") (pinfunction "Q7_7") (pintype "bidirectional"))
    )
    (net (code "113") (name "unconnected-(U6-Q7S-Pad9)") (class "Default")
      (node (ref "U6") (pin "9") (pinfunction "Q7S_9") (pintype "bidirectional"))
    )
  )
)
